# SCH_BLE-Watch.net
KiCad netlist of a schematic drawn in EasyEDA
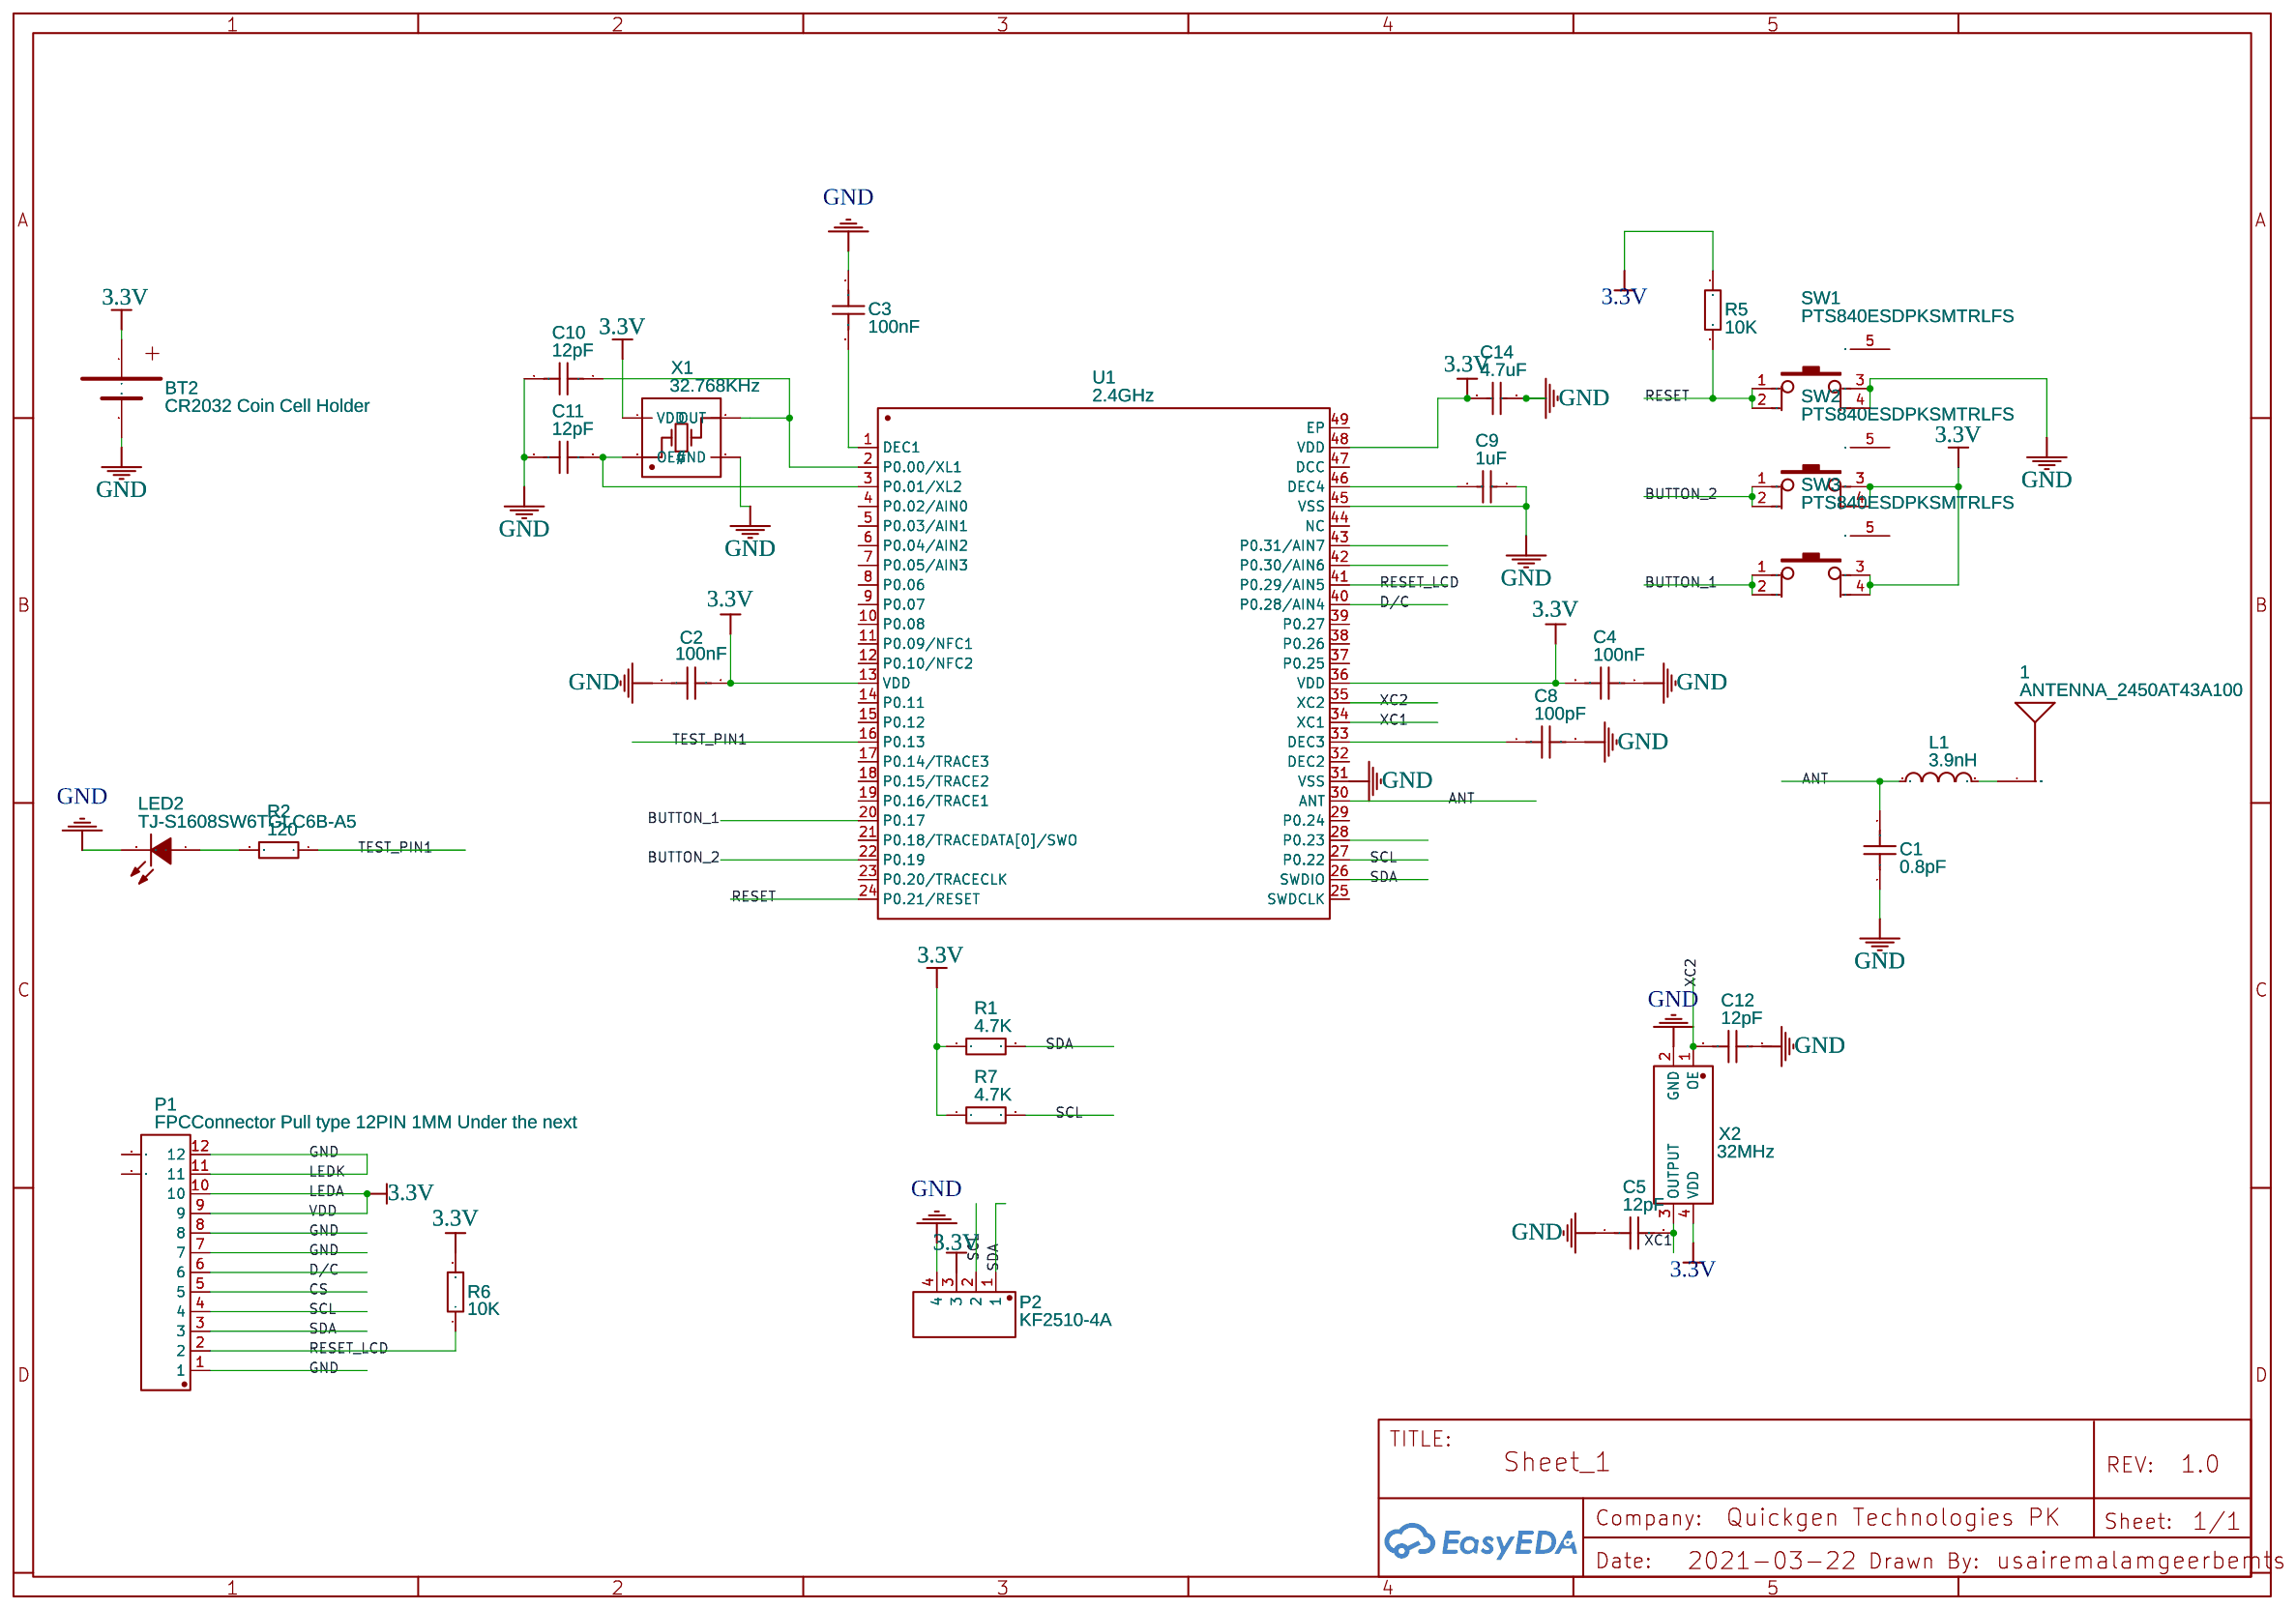
[diagram p0: schematic sheet]

(export (version "E")
  (design (tool "Eeschema 10.0.6"))
  (components
    (comp (ref "1") (value "ANTENNA_2450AT43A100") (libsource (lib "") (part "ANTENNA_2450AT43A100")))
    (comp (ref "BT2")
      (value "CR2032 Coin Cell Holder")
      (fields (field (name "Manufacturer Part") "BS-7 (2032 Coin Cell Holder)"))
      (libsource (lib "") (part "CR2032 Coin Cell Holder"))
    )
    (comp (ref "C1")
      (value "0.8pF")
      (fields (field (name "Manufacturer Part") "CC0402BRNPO9BNR80") (field (name "Manufacturer") "YAGEO"))
      (libsource (lib "") (part "CC0402BRNPO9BNR80"))
    )
    (comp (ref "C2")
      (value "100nF")
      (fields (field (name "Manufacturer Part") "CC0402KRX7R7BB104") (field (name "Manufacturer") "YAGEO"))
      (libsource (lib "") (part "CC0402KRX7R7BB104_1"))
    )
    (comp (ref "C3")
      (value "100nF")
      (fields (field (name "Manufacturer Part") "CC0402KRX7R7BB104") (field (name "Manufacturer") "YAGEO"))
      (libsource (lib "") (part "CC0402KRX7R7BB104_2"))
    )
    (comp (ref "C4")
      (value "100nF")
      (fields (field (name "Manufacturer Part") "CC0402KRX7R7BB104") (field (name "Manufacturer") "YAGEO"))
      (libsource (lib "") (part "CC0402KRX7R7BB104"))
    )
    (comp (ref "C5")
      (value "12pF")
      (fields
        (field (name "Manufacturer Part") "0402N120G500CT")
        (field (name "Manufacturer") "Walsin Tech Corp")
      )
      (libsource (lib "") (part "0402N120G500CT_1"))
    )
    (comp (ref "C8")
      (value "100pF")
      (fields (field (name "Manufacturer Part") "C1005NPO101JGT") (field (name "Manufacturer") "Darfon Elec"))
      (libsource (lib "") (part "C1005NPO101JGT"))
    )
    (comp (ref "C9")
      (value "1uF")
      (fields (field (name "Manufacturer Part") "CC0603KRX7R7BB105") (field (name "Manufacturer") "YAGEO"))
      (libsource (lib "") (part "CC0603KRX7R7BB105"))
    )
    (comp (ref "C10")
      (value "12pF")
      (fields
        (field (name "Manufacturer Part") "0402N120G500CT")
        (field (name "Manufacturer") "Walsin Tech Corp")
      )
      (libsource (lib "") (part "0402N120G500CT"))
    )
    (comp (ref "C11")
      (value "12pF")
      (fields
        (field (name "Manufacturer Part") "0402N120G500CT")
        (field (name "Manufacturer") "Walsin Tech Corp")
      )
      (libsource (lib "") (part "0402N120G500CT"))
    )
    (comp (ref "C12")
      (value "12pF")
      (fields
        (field (name "Manufacturer Part") "0402N120G500CT")
        (field (name "Manufacturer") "Walsin Tech Corp")
      )
      (libsource (lib "") (part "0402N120G500CT"))
    )
    (comp (ref "C14")
      (value "4.7uF")
      (fields (field (name "Manufacturer Part") "CC0603KRX5R6BB475") (field (name "Manufacturer") "YAGEO"))
      (libsource (lib "") (part "CC0603KRX5R6BB475"))
    )
    (comp (ref "L1")
      (value "3.9nH")
      (fields (field (name "Manufacturer Part") "SDWL1005C3N9JSTF") (field (name "Manufacturer") "Sunlord"))
      (libsource (lib "") (part "SDWL1005C3N9JSTF"))
    )
    (comp (ref "LED2")
      (value "TJ-S1608SW6TGLC6B-A5")
      (fields (field (name "Manufacturer") "TOGIALED"))
      (libsource (lib "") (part "TJ-S1608SW6TGLC6B-A5"))
    )
    (comp (ref "P1")
      (value "FPCConnector Pull type 12PIN 1MM Under the next")
      (fields (field (name "Manufacturer") "ReliaPro"))
      (libsource (lib "") (part "FPCConnector Pull type 12PIN 1MM Under the next"))
    )
    (comp (ref "P2")
      (value "KF2510-4A")
      (fields (field (name "Manufacturer") "ReliaPro"))
      (libsource (lib "") (part "KF2510-4A"))
    )
    (comp (ref "R1")
      (value "4.7K")
      (fields (field (name "Manufacturer Part") "RMS04JT472") (field (name "Manufacturer") "TA-I Tech"))
      (libsource (lib "") (part "RMS04JT472"))
    )
    (comp (ref "R2")
      (value "120")
      (fields (field (name "Manufacturer Part") "RMC04021201%N") (field (name "Manufacturer") "Tyohm"))
      (libsource (lib "") (part "RMC04021201%N"))
    )
    (comp (ref "R5")
      (value "10K")
      (fields (field (name "Manufacturer Part") "0402WGF1002TCE") (field (name "Manufacturer") "UniOhm"))
      (libsource (lib "") (part "0402WGF1002TCE"))
    )
    (comp (ref "R6")
      (value "10K")
      (fields
        (field (name "Manufacturer Part") "TC0225B1002TCE")
        (field (name "Manufacturer") "Uniroyal Elec")
      )
      (libsource (lib "") (part "TC0225B1002TCE"))
    )
    (comp (ref "R7")
      (value "4.7K")
      (fields (field (name "Manufacturer Part") "RMS04JT472") (field (name "Manufacturer") "TA-I Tech"))
      (libsource (lib "") (part "RMS04JT472"))
    )
    (comp (ref "SW1")
      (value "PTS840ESDPKSMTRLFS")
      (fields (field (name "Manufacturer") "C&K"))
      (libsource (lib "") (part "PTS840ESDPKSMTRLFS"))
    )
    (comp (ref "SW2")
      (value "PTS840ESDPKSMTRLFS")
      (fields (field (name "Manufacturer") "C&K"))
      (libsource (lib "") (part "PTS840ESDPKSMTRLFS"))
    )
    (comp (ref "SW3")
      (value "PTS840ESDPKSMTRLFS")
      (fields (field (name "Manufacturer") "C&K"))
      (libsource (lib "") (part "PTS840ESDPKSMTRLFS"))
    )
    (comp (ref "U1")
      (value "2.4GHz")
      (fields (field (name "Manufacturer Part") "NRF52832-QFAA-R") (field (name "Manufacturer") "NORDIC"))
      (libsource (lib "") (part "NRF52832-QFAA-R"))
    )
    (comp (ref "X1")
      (value "32.768KHz")
      (fields
        (field (name "Manufacturer Part") "3N00032G33YC")
        (field (name "Manufacturer") "SHENZHEN CRYSTAL TECH")
      )
      (libsource (lib "") (part "3N00032G33YC"))
    )
    (comp (ref "X2")
      (value "32MHz")
      (fields
        (field (name "Manufacturer Part") "S5D32.000000B20F30T")
        (field (name "Manufacturer") "Shenzhen SCTF Elec")
      )
      (libsource (lib "") (part "S5D32.000000B20F30T"))
    )
  )
  (nets
    (net (code "1") (name "/ANT") (class "Default")
      (node (ref "C1") (pin "2") (pinfunction "2_2") (pintype "unspecified"))
      (node (ref "L1") (pin "1") (pinfunction "1_1") (pintype "unspecified"))
      (node (ref "U1") (pin "30") (pinfunction "ANT_30") (pintype "unspecified"))
    )
    (net (code "2") (name "/BUTTON_1") (class "Default")
      (node (ref "SW3") (pin "1") (pinfunction "1_1") (pintype "input"))
      (node (ref "SW3") (pin "2") (pinfunction "2_2") (pintype "input"))
      (node (ref "U1") (pin "20") (pinfunction "P0.17_20") (pintype "unspecified"))
    )
    (net (code "3") (name "/BUTTON_2") (class "Default")
      (node (ref "SW2") (pin "1") (pinfunction "1_1") (pintype "input"))
      (node (ref "SW2") (pin "2") (pinfunction "2_2") (pintype "input"))
      (node (ref "U1") (pin "22") (pinfunction "P0.19_22") (pintype "unspecified"))
    )
    (net (code "4") (name "/CS") (class "Default")
      (node (ref "P1") (pin "5") (pinfunction "5_5") (pintype "unspecified"))
    )
    (net (code "5") (name "/D{slash}C") (class "Default")
      (node (ref "P1") (pin "6") (pinfunction "6_6") (pintype "unspecified"))
      (node (ref "U1") (pin "40") (pinfunction "P0.28/AIN4_40") (pintype "unspecified"))
    )
    (net (code "6") (name "/RESET") (class "Default")
      (node (ref "R5") (pin "1") (pinfunction "1_1") (pintype "input"))
      (node (ref "SW1") (pin "1") (pinfunction "1_1") (pintype "input"))
      (node (ref "SW1") (pin "2") (pinfunction "2_2") (pintype "input"))
      (node (ref "U1") (pin "24") (pinfunction "P0.21/RESET_24") (pintype "unspecified"))
    )
    (net (code "7") (name "/RESET_LCD") (class "Default")
      (node (ref "P1") (pin "2") (pinfunction "2_2") (pintype "unspecified"))
      (node (ref "R6") (pin "1") (pinfunction "1_1") (pintype "unspecified"))
      (node (ref "U1") (pin "41") (pinfunction "P0.29/AIN5_41") (pintype "unspecified"))
    )
    (net (code "8") (name "/SCL") (class "Default")
      (node (ref "P1") (pin "4") (pinfunction "4_4") (pintype "unspecified"))
      (node (ref "P2") (pin "2") (pinfunction "2_2") (pintype "unspecified"))
      (node (ref "R7") (pin "2") (pinfunction "2_2") (pintype "unspecified"))
      (node (ref "U1") (pin "27") (pinfunction "P0.22_27") (pintype "unspecified"))
    )
    (net (code "9") (name "/SDA") (class "Default")
      (node (ref "P1") (pin "3") (pinfunction "3_3") (pintype "unspecified"))
      (node (ref "P2") (pin "1") (pinfunction "1_1") (pintype "unspecified"))
      (node (ref "R1") (pin "2") (pinfunction "2_2") (pintype "unspecified"))
      (node (ref "U1") (pin "26") (pinfunction "SWDIO_26") (pintype "unspecified"))
    )
    (net (code "10") (name "/TEST_PIN1") (class "Default")
      (node (ref "R2") (pin "1") (pinfunction "1_1") (pintype "unspecified"))
      (node (ref "U1") (pin "16") (pinfunction "P0.13_16") (pintype "unspecified"))
    )
    (net (code "11") (name "/XC1") (class "Default")
      (node (ref "C5") (pin "2") (pinfunction "2_2") (pintype "unspecified"))
      (node (ref "U1") (pin "34") (pinfunction "XC1_34") (pintype "unspecified"))
      (node (ref "X2") (pin "3") (pinfunction "OUTPUT_3") (pintype "unspecified"))
    )
    (net (code "12") (name "/XC2") (class "Default")
      (node (ref "C12") (pin "2") (pinfunction "2_2") (pintype "unspecified"))
      (node (ref "U1") (pin "35") (pinfunction "XC2_35") (pintype "unspecified"))
      (node (ref "X2") (pin "1") (pinfunction "OE_1") (pintype "unspecified"))
    )
    (net (code "13") (name "3.3V") (class "Default")
      (node (ref "BT2") (pin "1") (pinfunction "1_1") (pintype "unspecified"))
      (node (ref "C14") (pin "2") (pinfunction "2_2") (pintype "input"))
      (node (ref "C2") (pin "2") (pinfunction "2_2") (pintype "unspecified"))
      (node (ref "C4") (pin "2") (pinfunction "2_2") (pintype "unspecified"))
      (node (ref "P1") (pin "10") (pinfunction "10_10") (pintype "unspecified"))
      (node (ref "P1") (pin "9") (pinfunction "9_9") (pintype "unspecified"))
      (node (ref "P2") (pin "3") (pinfunction "3_3") (pintype "unspecified"))
      (node (ref "R1") (pin "1") (pinfunction "1_1") (pintype "unspecified"))
      (node (ref "R5") (pin "2") (pinfunction "2_2") (pintype "input"))
      (node (ref "R6") (pin "2") (pinfunction "2_2") (pintype "unspecified"))
      (node (ref "R7") (pin "1") (pinfunction "1_1") (pintype "unspecified"))
      (node (ref "SW2") (pin "3") (pinfunction "3_3") (pintype "input"))
      (node (ref "SW2") (pin "4") (pinfunction "4_4") (pintype "input"))
      (node (ref "SW3") (pin "3") (pinfunction "3_3") (pintype "input"))
      (node (ref "SW3") (pin "4") (pinfunction "4_4") (pintype "input"))
      (node (ref "U1") (pin "13") (pinfunction "VDD_13") (pintype "unspecified"))
      (node (ref "U1") (pin "36") (pinfunction "VDD_36") (pintype "unspecified"))
      (node (ref "U1") (pin "48") (pinfunction "VDD_48") (pintype "unspecified"))
      (node (ref "X1") (pin "4") (pinfunction "VDD_4") (pintype "input"))
      (node (ref "X2") (pin "4") (pinfunction "VDD_4") (pintype "unspecified"))
    )
    (net (code "14") (name "GND") (class "Default")
      (node (ref "BT2") (pin "2") (pinfunction "2_2") (pintype "unspecified"))
      (node (ref "C1") (pin "1") (pinfunction "1_1") (pintype "unspecified"))
      (node (ref "C10") (pin "2") (pinfunction "2_2") (pintype "unspecified"))
      (node (ref "C11") (pin "2") (pinfunction "2_2") (pintype "unspecified"))
      (node (ref "C12") (pin "1") (pinfunction "1_1") (pintype "unspecified"))
      (node (ref "C14") (pin "1") (pinfunction "1_1") (pintype "input"))
      (node (ref "C2") (pin "1") (pinfunction "1_1") (pintype "unspecified"))
      (node (ref "C3") (pin "1") (pinfunction "1_1") (pintype "unspecified"))
      (node (ref "C4") (pin "1") (pinfunction "1_1") (pintype "unspecified"))
      (node (ref "C5") (pin "1") (pinfunction "1_1") (pintype "unspecified"))
      (node (ref "C8") (pin "2") (pinfunction "2_2") (pintype "unspecified"))
      (node (ref "C9") (pin "2") (pinfunction "2_2") (pintype "input"))
      (node (ref "LED2") (pin "2") (pinfunction "K_2") (pintype "unspecified"))
      (node (ref "P1") (pin "1") (pinfunction "1_1") (pintype "unspecified"))
      (node (ref "P1") (pin "11") (pinfunction "11_11") (pintype "unspecified"))
      (node (ref "P1") (pin "12") (pinfunction "12_12") (pintype "unspecified"))
      (node (ref "P1") (pin "7") (pinfunction "7_7") (pintype "unspecified"))
      (node (ref "P1") (pin "8") (pinfunction "8_8") (pintype "unspecified"))
      (node (ref "P2") (pin "4") (pinfunction "4_4") (pintype "unspecified"))
      (node (ref "SW1") (pin "3") (pinfunction "3_3") (pintype "input"))
      (node (ref "SW1") (pin "4") (pinfunction "4_4") (pintype "input"))
      (node (ref "U1") (pin "31") (pinfunction "VSS_31") (pintype "unspecified"))
      (node (ref "U1") (pin "45") (pinfunction "VSS_45") (pintype "unspecified"))
      (node (ref "X1") (pin "2") (pinfunction "GND_2") (pintype "input"))
      (node (ref "X2") (pin "2") (pinfunction "GND_2") (pintype "unspecified"))
    )
    (net (code "15") (name "Net-(1-P$1)") (class "Default")
      (node (ref "1") (pin "1") (pinfunction "P$1_1") (pintype "bidirectional"))
      (node (ref "L1") (pin "2") (pinfunction "2_2") (pintype "unspecified"))
    )
    (net (code "16") (name "Net-(LED2-A)") (class "Default")
      (node (ref "LED2") (pin "1") (pinfunction "A_1") (pintype "unspecified"))
      (node (ref "R2") (pin "2") (pinfunction "2_2") (pintype "unspecified"))
    )
    (net (code "17") (name "Net-(U1-DEC1)") (class "Default")
      (node (ref "C3") (pin "2") (pinfunction "2_2") (pintype "unspecified"))
      (node (ref "U1") (pin "1") (pinfunction "DEC1_1") (pintype "unspecified"))
    )
    (net (code "18") (name "Net-(U1-DEC3)") (class "Default")
      (node (ref "C8") (pin "1") (pinfunction "1_1") (pintype "unspecified"))
      (node (ref "U1") (pin "33") (pinfunction "DEC3_33") (pintype "unspecified"))
    )
    (net (code "19") (name "Net-(U1-DEC4)") (class "Default")
      (node (ref "C9") (pin "1") (pinfunction "1_1") (pintype "input"))
      (node (ref "U1") (pin "46") (pinfunction "DEC4_46") (pintype "unspecified"))
    )
    (net (code "20") (name "Net-(U1-P0.00{slash}XL1)") (class "Default")
      (node (ref "C10") (pin "1") (pinfunction "1_1") (pintype "unspecified"))
      (node (ref "U1") (pin "2") (pinfunction "P0.00/XL1_2") (pintype "unspecified"))
      (node (ref "X1") (pin "3") (pinfunction "OUT_3") (pintype "input"))
    )
    (net (code "21") (name "Net-(U1-P0.01{slash}XL2)") (class "Default")
      (node (ref "C11") (pin "1") (pinfunction "1_1") (pintype "unspecified"))
      (node (ref "U1") (pin "3") (pinfunction "P0.01/XL2_3") (pintype "unspecified"))
      (node (ref "X1") (pin "1") (pinfunction "OE#_1") (pintype "input"))
    )
    (net (code "22") (name "unconnected-(P1-Pad13)") (class "Default")
      (node (ref "P1") (pin "13") (pinfunction "13_13") (pintype "unspecified"))
    )
    (net (code "23") (name "unconnected-(P1-Pad14)") (class "Default")
      (node (ref "P1") (pin "14") (pinfunction "14_14") (pintype "unspecified"))
    )
    (net (code "24") (name "unconnected-(SW1-Pad5)") (class "Default")
      (node (ref "SW1") (pin "5") (pinfunction "5_5") (pintype "unspecified"))
    )
    (net (code "25") (name "unconnected-(SW2-Pad5)") (class "Default")
      (node (ref "SW2") (pin "5") (pinfunction "5_5") (pintype "unspecified"))
    )
    (net (code "26") (name "unconnected-(SW3-Pad5)") (class "Default")
      (node (ref "SW3") (pin "5") (pinfunction "5_5") (pintype "unspecified"))
    )
    (net (code "27") (name "unconnected-(U1-DCC-Pad47)") (class "Default")
      (node (ref "U1") (pin "47") (pinfunction "DCC_47") (pintype "unspecified"))
    )
    (net (code "28") (name "unconnected-(U1-DEC2-Pad32)") (class "Default")
      (node (ref "U1") (pin "32") (pinfunction "DEC2_32") (pintype "unspecified"))
    )
    (net (code "29") (name "unconnected-(U1-EP-Pad49)") (class "Default")
      (node (ref "U1") (pin "49") (pinfunction "EP_49") (pintype "unspecified"))
    )
    (net (code "30") (name "unconnected-(U1-NC-Pad44)") (class "Default")
      (node (ref "U1") (pin "44") (pinfunction "NC_44") (pintype "unspecified"))
    )
    (net (code "31") (name "unconnected-(U1-P0.02{slash}AIN0-Pad4)") (class "Default")
      (node (ref "U1") (pin "4") (pinfunction "P0.02/AIN0_4") (pintype "unspecified"))
    )
    (net (code "32") (name "unconnected-(U1-P0.03{slash}AIN1-Pad5)") (class "Default")
      (node (ref "U1") (pin "5") (pinfunction "P0.03/AIN1_5") (pintype "unspecified"))
    )
    (net (code "33") (name "unconnected-(U1-P0.04{slash}AIN2-Pad6)") (class "Default")
      (node (ref "U1") (pin "6") (pinfunction "P0.04/AIN2_6") (pintype "unspecified"))
    )
    (net (code "34") (name "unconnected-(U1-P0.05{slash}AIN3-Pad7)") (class "Default")
      (node (ref "U1") (pin "7") (pinfunction "P0.05/AIN3_7") (pintype "unspecified"))
    )
    (net (code "35") (name "unconnected-(U1-P0.06-Pad8)") (class "Default")
      (node (ref "U1") (pin "8") (pinfunction "P0.06_8") (pintype "unspecified"))
    )
    (net (code "36") (name "unconnected-(U1-P0.07-Pad9)") (class "Default")
      (node (ref "U1") (pin "9") (pinfunction "P0.07_9") (pintype "unspecified"))
    )
    (net (code "37") (name "unconnected-(U1-P0.08-Pad10)") (class "Default")
      (node (ref "U1") (pin "10") (pinfunction "P0.08_10") (pintype "unspecified"))
    )
    (net (code "38") (name "unconnected-(U1-P0.09{slash}NFC1-Pad11)") (class "Default")
      (node (ref "U1") (pin "11") (pinfunction "P0.09/NFC1_11") (pintype "unspecified"))
    )
    (net (code "39") (name "unconnected-(U1-P0.10{slash}NFC2-Pad12)") (class "Default")
      (node (ref "U1") (pin "12") (pinfunction "P0.10/NFC2_12") (pintype "unspecified"))
    )
    (net (code "40") (name "unconnected-(U1-P0.11-Pad14)") (class "Default")
      (node (ref "U1") (pin "14") (pinfunction "P0.11_14") (pintype "unspecified"))
    )
    (net (code "41") (name "unconnected-(U1-P0.12-Pad15)") (class "Default")
      (node (ref "U1") (pin "15") (pinfunction "P0.12_15") (pintype "unspecified"))
    )
    (net (code "42") (name "unconnected-(U1-P0.14{slash}TRACE3-Pad17)") (class "Default")
      (node (ref "U1") (pin "17") (pinfunction "P0.14/TRACE3_17") (pintype "unspecified"))
    )
    (net (code "43") (name "unconnected-(U1-P0.15{slash}TRACE2-Pad18)") (class "Default")
      (node (ref "U1") (pin "18") (pinfunction "P0.15/TRACE2_18") (pintype "unspecified"))
    )
    (net (code "44") (name "unconnected-(U1-P0.16{slash}TRACE1-Pad19)") (class "Default")
      (node (ref "U1") (pin "19") (pinfunction "P0.16/TRACE1_19") (pintype "unspecified"))
    )
    (net (code "45") (name "unconnected-(U1-P0.18{slash}TRACEDATA[0]{slash}SWO-Pad21)") (class "Default")
      (node (ref "U1") (pin "21") (pinfunction "P0.18/TRACEDATA[0]/SWO_21") (pintype "unspecified"))
    )
    (net (code "46") (name "unconnected-(U1-P0.20{slash}TRACECLK-Pad23)") (class "Default")
      (node (ref "U1") (pin "23") (pinfunction "P0.20/TRACECLK_23") (pintype "unspecified"))
    )
    (net (code "47") (name "unconnected-(U1-P0.23-Pad28)") (class "Default")
      (node (ref "U1") (pin "28") (pinfunction "P0.23_28") (pintype "unspecified"))
    )
    (net (code "48") (name "unconnected-(U1-P0.24-Pad29)") (class "Default")
      (node (ref "U1") (pin "29") (pinfunction "P0.24_29") (pintype "unspecified"))
    )
    (net (code "49") (name "unconnected-(U1-P0.25-Pad37)") (class "Default")
      (node (ref "U1") (pin "37") (pinfunction "P0.25_37") (pintype "unspecified"))
    )
    (net (code "50") (name "unconnected-(U1-P0.26-Pad38)") (class "Default")
      (node (ref "U1") (pin "38") (pinfunction "P0.26_38") (pintype "unspecified"))
    )
    (net (code "51") (name "unconnected-(U1-P0.27-Pad39)") (class "Default")
      (node (ref "U1") (pin "39") (pinfunction "P0.27_39") (pintype "unspecified"))
    )
    (net (code "52") (name "unconnected-(U1-P0.30{slash}AIN6-Pad42)") (class "Default")
      (node (ref "U1") (pin "42") (pinfunction "P0.30/AIN6_42") (pintype "unspecified"))
    )
    (net (code "53") (name "unconnected-(U1-P0.31{slash}AIN7-Pad43)") (class "Default")
      (node (ref "U1") (pin "43") (pinfunction "P0.31/AIN7_43") (pintype "unspecified"))
    )
    (net (code "54") (name "unconnected-(U1-SWDCLK-Pad25)") (class "Default")
      (node (ref "U1") (pin "25") (pinfunction "SWDCLK_25") (pintype "unspecified"))
    )
  )
)
